# Sheet_1_2022-06-08.net
KiCad netlist of a schematic drawn in Altium Designer
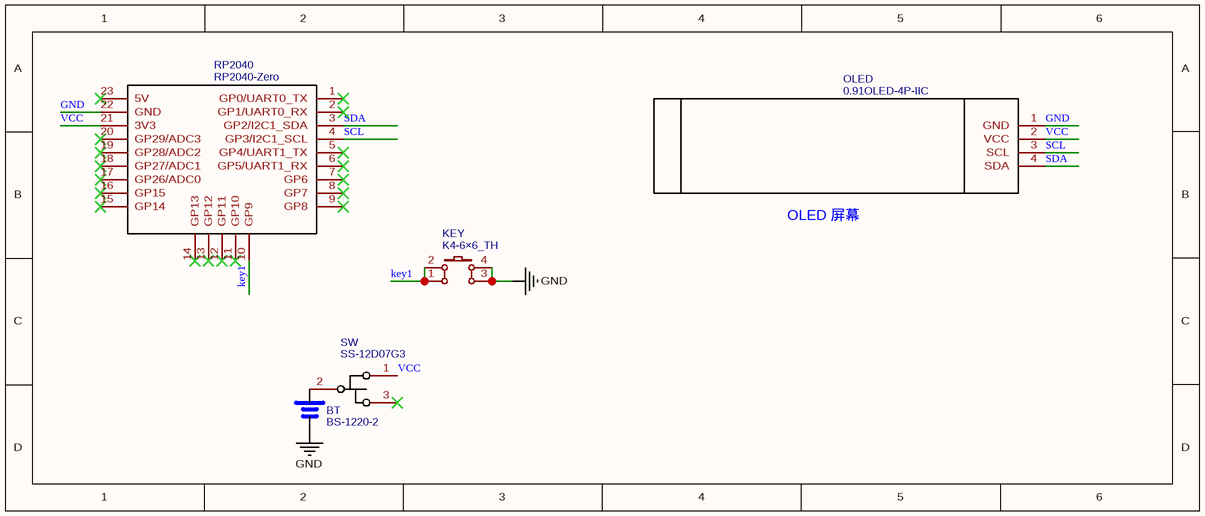
[diagram p0: Sheet_1_2022-06-08.schdoc]

(export (version "E")
  (design (tool "Eeschema 10.0.6"))
  (components
    (comp (ref "BT")
      (value "BS-1220-2")
      (fields (field (name "CONTRIBUTOR") "18868726200"))
      (libsource (lib "altium-import") (part "root_0_BS-1220-2_"))
    )
    (comp (ref "KEY")
      (value "K4-6×6_TH")
      (fields
        (field (name "BOM_SUPPLIER PART") "C136684")
        (field (name "BOM_MANUFACTURER PART") "K2-1102DP-E4SW-04")
        (field (name "CONTRIBUTOR") "LCEDA_Lib")
      )
      (libsource (lib "altium-import") (part "root_0_K4-6×6_TH_"))
    )
    (comp (ref "OLED")
      (value "0.91OLED-4P-IIC")
      (fields (field (name "CONTRIBUTOR") "lemondx"))
      (libsource (lib "altium-import") (part "root_2_0.91OLED-4P-IIC_"))
    )
    (comp (ref "RP2040")
      (value "RP2040-Zero")
      (fields (field (name "CONTRIBUTOR") "MoyunHui"))
      (libsource (lib "altium-import") (part "root_0_RP2040-Zero_"))
    )
    (comp (ref "SW")
      (value "SS-12D07G3")
      (fields (field (name "BOM_SUPPLIER PART") "C64633") (field (name "CONTRIBUTOR") "技小新团队"))
      (libsource (lib "altium-import") (part "root_0_SS-12D07G3_"))
    )
  )
  (nets
    (net (code "1") (name "/SCL") (class "Default")
      (node (ref "OLED") (pin "3") (pinfunction "SCL_3") (pintype "passive"))
      (node (ref "RP2040") (pin "4") (pinfunction "GP3/I2C1_SCL_4") (pintype "passive"))
    )
    (net (code "2") (name "/SDA") (class "Default")
      (node (ref "OLED") (pin "4") (pinfunction "SDA_4") (pintype "passive"))
      (node (ref "RP2040") (pin "3") (pinfunction "GP2/I2C1_SDA_3") (pintype "passive"))
    )
    (net (code "3") (name "/VCC") (class "Default")
      (node (ref "OLED") (pin "2") (pinfunction "VCC_2") (pintype "passive"))
      (node (ref "RP2040") (pin "21") (pinfunction "3V3_21") (pintype "passive"))
      (node (ref "SW") (pin "1") (pinfunction "1_1") (pintype "passive"))
    )
    (net (code "4") (name "/key1") (class "Default")
      (node (ref "KEY") (pin "1") (pinfunction "1_1") (pintype "passive"))
      (node (ref "KEY") (pin "2") (pinfunction "2_2") (pintype "passive"))
      (node (ref "RP2040") (pin "10") (pinfunction "GP9_10") (pintype "passive"))
    )
    (net (code "5") (name "GND") (class "Default")
      (node (ref "BT") (pin "2") (pintype "passive"))
      (node (ref "KEY") (pin "3") (pinfunction "3_3") (pintype "passive"))
      (node (ref "KEY") (pin "4") (pinfunction "4_4") (pintype "passive"))
      (node (ref "OLED") (pin "1") (pinfunction "GND_1") (pintype "passive"))
      (node (ref "RP2040") (pin "22") (pinfunction "GND_22") (pintype "passive"))
    )
    (net (code "6") (name "Net-(BT-Pad1)") (class "Default")
      (node (ref "BT") (pin "1") (pintype "passive"))
      (node (ref "SW") (pin "2") (pinfunction "2_2") (pintype "passive"))
    )
    (net (code "7") (name "unconnected-(RP2040-5V-Pad23)") (class "Default")
      (node (ref "RP2040") (pin "23") (pinfunction "5V_23") (pintype "passive+no_connect"))
    )
    (net (code "8") (name "unconnected-(RP2040-GP0{slash}UART0_TX-Pad1)") (class "Default")
      (node (ref "RP2040") (pin "1") (pinfunction "GP0/UART0_TX_1") (pintype "passive+no_connect"))
    )
    (net (code "9") (name "unconnected-(RP2040-GP1{slash}UART0_RX-Pad2)") (class "Default")
      (node (ref "RP2040") (pin "2") (pinfunction "GP1/UART0_RX_2") (pintype "passive+no_connect"))
    )
    (net (code "10") (name "unconnected-(RP2040-GP4{slash}UART1_TX-Pad5)") (class "Default")
      (node (ref "RP2040") (pin "5") (pinfunction "GP4/UART1_TX_5") (pintype "passive+no_connect"))
    )
    (net (code "11") (name "unconnected-(RP2040-GP5{slash}UART1_RX-Pad6)") (class "Default")
      (node (ref "RP2040") (pin "6") (pinfunction "GP5/UART1_RX_6") (pintype "passive+no_connect"))
    )
    (net (code "12") (name "unconnected-(RP2040-GP6-Pad7)") (class "Default")
      (node (ref "RP2040") (pin "7") (pinfunction "GP6_7") (pintype "passive+no_connect"))
    )
    (net (code "13") (name "unconnected-(RP2040-GP7-Pad8)") (class "Default")
      (node (ref "RP2040") (pin "8") (pinfunction "GP7_8") (pintype "passive+no_connect"))
    )
    (net (code "14") (name "unconnected-(RP2040-GP8-Pad9)") (class "Default")
      (node (ref "RP2040") (pin "9") (pinfunction "GP8_9") (pintype "passive+no_connect"))
    )
    (net (code "15") (name "unconnected-(RP2040-GP10-Pad11)") (class "Default")
      (node (ref "RP2040") (pin "11") (pinfunction "GP10_11") (pintype "passive+no_connect"))
    )
    (net (code "16") (name "unconnected-(RP2040-GP11-Pad12)") (class "Default")
      (node (ref "RP2040") (pin "12") (pinfunction "GP11_12") (pintype "passive+no_connect"))
    )
    (net (code "17") (name "unconnected-(RP2040-GP12-Pad13)") (class "Default")
      (node (ref "RP2040") (pin "13") (pinfunction "GP12_13") (pintype "passive+no_connect"))
    )
    (net (code "18") (name "unconnected-(RP2040-GP13-Pad14)") (class "Default")
      (node (ref "RP2040") (pin "14") (pinfunction "GP13_14") (pintype "passive+no_connect"))
    )
    (net (code "19") (name "unconnected-(RP2040-GP14-Pad15)") (class "Default")
      (node (ref "RP2040") (pin "15") (pinfunction "GP14_15") (pintype "passive+no_connect"))
    )
    (net (code "20") (name "unconnected-(RP2040-GP15-Pad16)") (class "Default")
      (node (ref "RP2040") (pin "16") (pinfunction "GP15_16") (pintype "passive+no_connect"))
    )
    (net (code "21") (name "unconnected-(RP2040-GP26{slash}ADC0-Pad17)") (class "Default")
      (node (ref "RP2040") (pin "17") (pinfunction "GP26/ADC0_17") (pintype "passive+no_connect"))
    )
    (net (code "22") (name "unconnected-(RP2040-GP27{slash}ADC1-Pad18)") (class "Default")
      (node (ref "RP2040") (pin "18") (pinfunction "GP27/ADC1_18") (pintype "passive+no_connect"))
    )
    (net (code "23") (name "unconnected-(RP2040-GP28{slash}ADC2-Pad19)") (class "Default")
      (node (ref "RP2040") (pin "19") (pinfunction "GP28/ADC2_19") (pintype "passive+no_connect"))
    )
    (net (code "24") (name "unconnected-(RP2040-GP29{slash}ADC3-Pad20)") (class "Default")
      (node (ref "RP2040") (pin "20") (pinfunction "GP29/ADC3_20") (pintype "passive+no_connect"))
    )
    (net (code "25") (name "unconnected-(SW-Pad3)") (class "Default")
      (node (ref "SW") (pin "3") (pinfunction "3_3") (pintype "passive+no_connect"))
    )
  )
)
